# TCA_LP_FILTER.net
KiCad netlist of a schematic drawn in Altium Designer
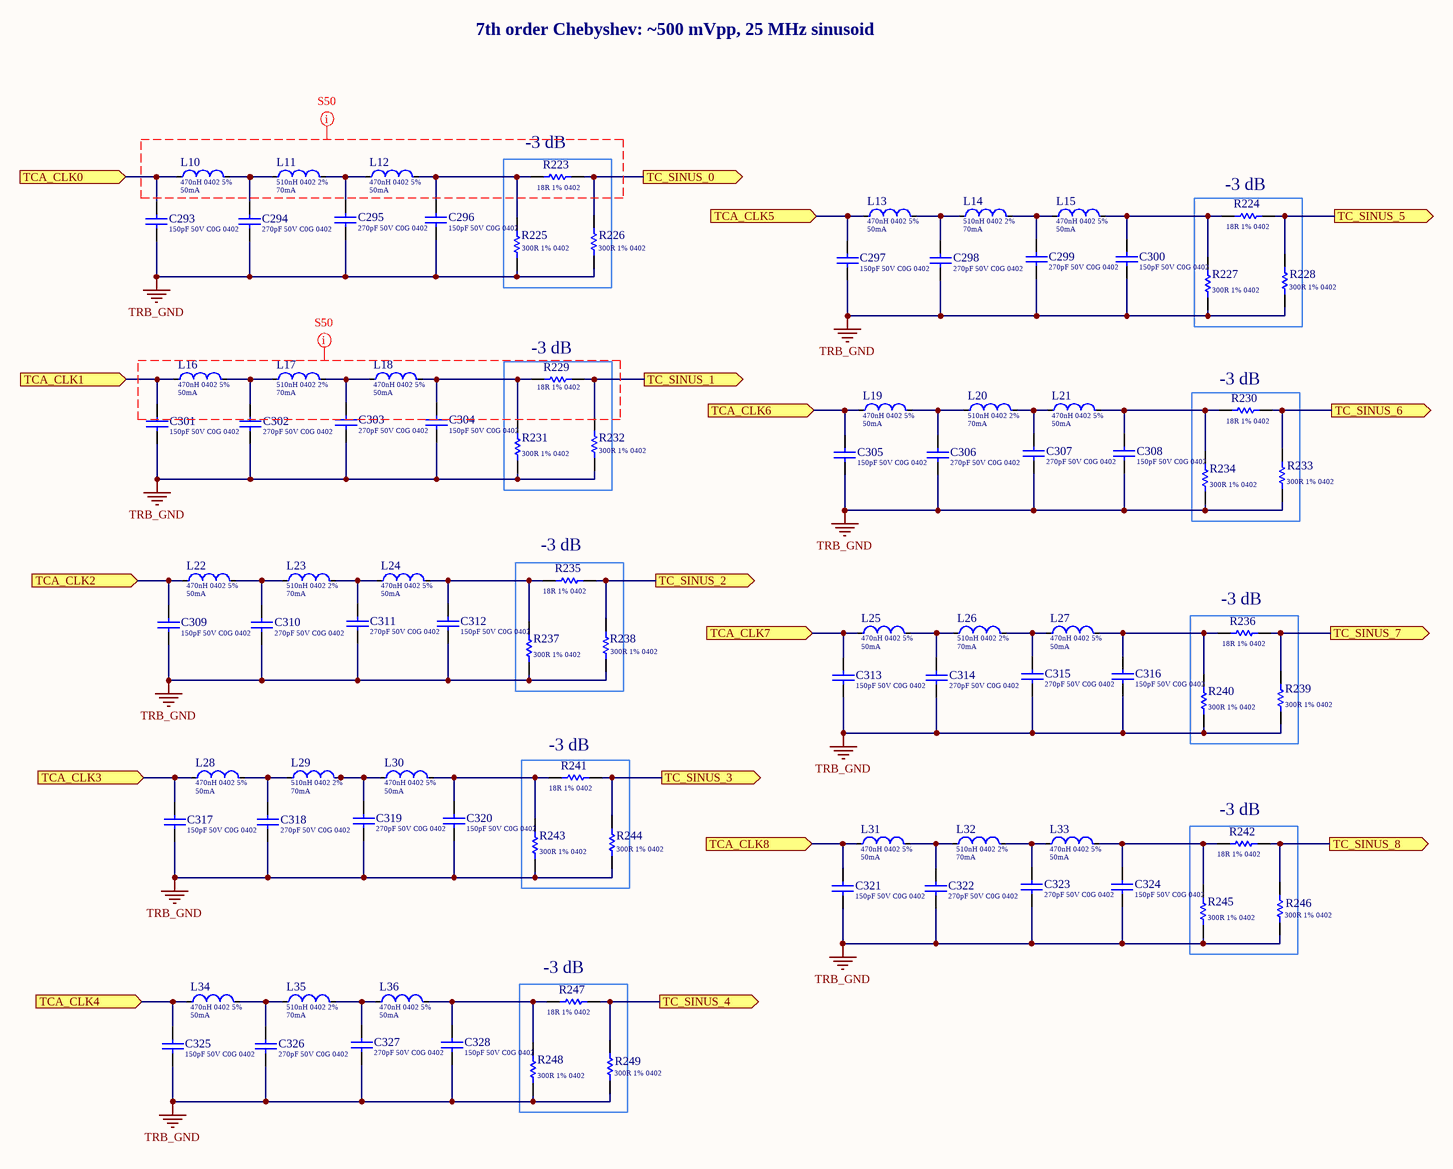
[diagram p0: TCA_LP_FILTER.SchDoc]

(export (version "E")
  (design (tool "Eeschema 10.0.6"))
  (components
    (comp (ref "C293")
      (value "Cap_TDK_CGA2B2C0G2A151J050BE_150pF")
      (footprint "Cap_TDK_CGA2B2C0G2A151J050BE_150pF")
      (description "CAP 150pF 50V C0G ±1% 0402 (1000 Metric) Thickness 1mm SMD")
      (fields (field (name "CAPACITANCE") "150pF 50V C0G 0402"))
      (libsource (lib "Cap_TDK_CGA2B2C0G2A151J050BE_150pF") (part "Cap_TDK_CGA2B2C0G2A151J050BE_150pF"))
    )
    (comp (ref "C294")
      (value "Cap_Murata_GCM1555C1H271FA16D_270pF")
      (footprint "Cap_Murata_GCM1555C1H271FA16D_270pF")
      (description "CAP 270pF 50V C0G ±1% 0402")
      (fields (field (name "CAPACITANCE") "270pF 50V C0G 0402"))
      (libsource (lib "Cap_Murata_GCM1555C1H271FA16D_270pF") (part "Cap_Murata_GCM1555C1H271FA16D_270pF"))
    )
    (comp (ref "C295")
      (value "Cap_Murata_GCM1555C1H271FA16D_270pF")
      (footprint "Cap_Murata_GCM1555C1H271FA16D_270pF")
      (description "CAP 270pF 50V C0G ±1% 0402")
      (fields (field (name "CAPACITANCE") "270pF 50V C0G 0402"))
      (libsource (lib "Cap_Murata_GCM1555C1H271FA16D_270pF") (part "Cap_Murata_GCM1555C1H271FA16D_270pF"))
    )
    (comp (ref "C296")
      (value "Cap_TDK_CGA2B2C0G2A151J050BE_150pF")
      (footprint "Cap_TDK_CGA2B2C0G2A151J050BE_150pF")
      (description "CAP 150pF 50V C0G ±1% 0402 (1000 Metric) Thickness 1mm SMD")
      (fields (field (name "CAPACITANCE") "150pF 50V C0G 0402"))
      (libsource (lib "Cap_TDK_CGA2B2C0G2A151J050BE_150pF") (part "Cap_TDK_CGA2B2C0G2A151J050BE_150pF"))
    )
    (comp (ref "C297")
      (value "Cap_TDK_CGA2B2C0G2A151J050BE_150pF")
      (footprint "Cap_TDK_CGA2B2C0G2A151J050BE_150pF")
      (description "CAP 150pF 50V C0G ±1% 0402 (1000 Metric) Thickness 1mm SMD")
      (fields (field (name "CAPACITANCE") "150pF 50V C0G 0402"))
      (libsource (lib "Cap_TDK_CGA2B2C0G2A151J050BE_150pF") (part "Cap_TDK_CGA2B2C0G2A151J050BE_150pF"))
    )
    (comp (ref "C298")
      (value "Cap_Murata_GCM1555C1H271FA16D_270pF")
      (footprint "Cap_Murata_GCM1555C1H271FA16D_270pF")
      (description "CAP 270pF 50V C0G ±1% 0402")
      (fields (field (name "CAPACITANCE") "270pF 50V C0G 0402"))
      (libsource (lib "Cap_Murata_GCM1555C1H271FA16D_270pF") (part "Cap_Murata_GCM1555C1H271FA16D_270pF"))
    )
    (comp (ref "C299")
      (value "Cap_Murata_GCM1555C1H271FA16D_270pF")
      (footprint "Cap_Murata_GCM1555C1H271FA16D_270pF")
      (description "CAP 270pF 50V C0G ±1% 0402")
      (fields (field (name "CAPACITANCE") "270pF 50V C0G 0402"))
      (libsource (lib "Cap_Murata_GCM1555C1H271FA16D_270pF") (part "Cap_Murata_GCM1555C1H271FA16D_270pF"))
    )
    (comp (ref "C300")
      (value "Cap_TDK_CGA2B2C0G2A151J050BE_150pF")
      (footprint "Cap_TDK_CGA2B2C0G2A151J050BE_150pF")
      (description "CAP 150pF 50V C0G ±1% 0402 (1000 Metric) Thickness 1mm SMD")
      (fields (field (name "CAPACITANCE") "150pF 50V C0G 0402"))
      (libsource (lib "Cap_TDK_CGA2B2C0G2A151J050BE_150pF") (part "Cap_TDK_CGA2B2C0G2A151J050BE_150pF"))
    )
    (comp (ref "C301")
      (value "Cap_TDK_CGA2B2C0G2A151J050BE_150pF")
      (footprint "Cap_TDK_CGA2B2C0G2A151J050BE_150pF")
      (description "CAP 150pF 50V C0G ±1% 0402 (1000 Metric) Thickness 1mm SMD")
      (fields (field (name "CAPACITANCE") "150pF 50V C0G 0402"))
      (libsource (lib "Cap_TDK_CGA2B2C0G2A151J050BE_150pF") (part "Cap_TDK_CGA2B2C0G2A151J050BE_150pF"))
    )
    (comp (ref "C302")
      (value "Cap_Murata_GCM1555C1H271FA16D_270pF")
      (footprint "Cap_Murata_GCM1555C1H271FA16D_270pF")
      (description "CAP 270pF 50V C0G ±1% 0402")
      (fields (field (name "CAPACITANCE") "270pF 50V C0G 0402"))
      (libsource (lib "Cap_Murata_GCM1555C1H271FA16D_270pF") (part "Cap_Murata_GCM1555C1H271FA16D_270pF"))
    )
    (comp (ref "C303")
      (value "Cap_Murata_GCM1555C1H271FA16D_270pF")
      (footprint "Cap_Murata_GCM1555C1H271FA16D_270pF")
      (description "CAP 270pF 50V C0G ±1% 0402")
      (fields (field (name "CAPACITANCE") "270pF 50V C0G 0402"))
      (libsource (lib "Cap_Murata_GCM1555C1H271FA16D_270pF") (part "Cap_Murata_GCM1555C1H271FA16D_270pF"))
    )
    (comp (ref "C304")
      (value "Cap_TDK_CGA2B2C0G2A151J050BE_150pF")
      (footprint "Cap_TDK_CGA2B2C0G2A151J050BE_150pF")
      (description "CAP 150pF 50V C0G ±1% 0402 (1000 Metric) Thickness 1mm SMD")
      (fields (field (name "CAPACITANCE") "150pF 50V C0G 0402"))
      (libsource (lib "Cap_TDK_CGA2B2C0G2A151J050BE_150pF") (part "Cap_TDK_CGA2B2C0G2A151J050BE_150pF"))
    )
    (comp (ref "C305")
      (value "Cap_TDK_CGA2B2C0G2A151J050BE_150pF")
      (footprint "Cap_TDK_CGA2B2C0G2A151J050BE_150pF")
      (description "CAP 150pF 50V C0G ±1% 0402 (1000 Metric) Thickness 1mm SMD")
      (fields (field (name "CAPACITANCE") "150pF 50V C0G 0402"))
      (libsource (lib "Cap_TDK_CGA2B2C0G2A151J050BE_150pF") (part "Cap_TDK_CGA2B2C0G2A151J050BE_150pF"))
    )
    (comp (ref "C306")
      (value "Cap_Murata_GCM1555C1H271FA16D_270pF")
      (footprint "Cap_Murata_GCM1555C1H271FA16D_270pF")
      (description "CAP 270pF 50V C0G ±1% 0402")
      (fields (field (name "CAPACITANCE") "270pF 50V C0G 0402"))
      (libsource (lib "Cap_Murata_GCM1555C1H271FA16D_270pF") (part "Cap_Murata_GCM1555C1H271FA16D_270pF"))
    )
    (comp (ref "C307")
      (value "Cap_Murata_GCM1555C1H271FA16D_270pF")
      (footprint "Cap_Murata_GCM1555C1H271FA16D_270pF")
      (description "CAP 270pF 50V C0G ±1% 0402")
      (fields (field (name "CAPACITANCE") "270pF 50V C0G 0402"))
      (libsource (lib "Cap_Murata_GCM1555C1H271FA16D_270pF") (part "Cap_Murata_GCM1555C1H271FA16D_270pF"))
    )
    (comp (ref "C308")
      (value "Cap_TDK_CGA2B2C0G2A151J050BE_150pF")
      (footprint "Cap_TDK_CGA2B2C0G2A151J050BE_150pF")
      (description "CAP 150pF 50V C0G ±1% 0402 (1000 Metric) Thickness 1mm SMD")
      (fields (field (name "CAPACITANCE") "150pF 50V C0G 0402"))
      (libsource (lib "Cap_TDK_CGA2B2C0G2A151J050BE_150pF") (part "Cap_TDK_CGA2B2C0G2A151J050BE_150pF"))
    )
    (comp (ref "C309")
      (value "Cap_TDK_CGA2B2C0G2A151J050BE_150pF")
      (footprint "Cap_TDK_CGA2B2C0G2A151J050BE_150pF")
      (description "CAP 150pF 50V C0G ±1% 0402 (1000 Metric) Thickness 1mm SMD")
      (fields (field (name "CAPACITANCE") "150pF 50V C0G 0402"))
      (libsource (lib "Cap_TDK_CGA2B2C0G2A151J050BE_150pF") (part "Cap_TDK_CGA2B2C0G2A151J050BE_150pF"))
    )
    (comp (ref "C310")
      (value "Cap_Murata_GCM1555C1H271FA16D_270pF")
      (footprint "Cap_Murata_GCM1555C1H271FA16D_270pF")
      (description "CAP 270pF 50V C0G ±1% 0402")
      (fields (field (name "CAPACITANCE") "270pF 50V C0G 0402"))
      (libsource (lib "Cap_Murata_GCM1555C1H271FA16D_270pF") (part "Cap_Murata_GCM1555C1H271FA16D_270pF"))
    )
    (comp (ref "C311")
      (value "Cap_Murata_GCM1555C1H271FA16D_270pF")
      (footprint "Cap_Murata_GCM1555C1H271FA16D_270pF")
      (description "CAP 270pF 50V C0G ±1% 0402")
      (fields (field (name "CAPACITANCE") "270pF 50V C0G 0402"))
      (libsource (lib "Cap_Murata_GCM1555C1H271FA16D_270pF") (part "Cap_Murata_GCM1555C1H271FA16D_270pF"))
    )
    (comp (ref "C312")
      (value "Cap_TDK_CGA2B2C0G2A151J050BE_150pF")
      (footprint "Cap_TDK_CGA2B2C0G2A151J050BE_150pF")
      (description "CAP 150pF 50V C0G ±1% 0402 (1000 Metric) Thickness 1mm SMD")
      (fields (field (name "CAPACITANCE") "150pF 50V C0G 0402"))
      (libsource (lib "Cap_TDK_CGA2B2C0G2A151J050BE_150pF") (part "Cap_TDK_CGA2B2C0G2A151J050BE_150pF"))
    )
    (comp (ref "C313")
      (value "Cap_TDK_CGA2B2C0G2A151J050BE_150pF")
      (footprint "Cap_TDK_CGA2B2C0G2A151J050BE_150pF")
      (description "CAP 150pF 50V C0G ±1% 0402 (1000 Metric) Thickness 1mm SMD")
      (fields (field (name "CAPACITANCE") "150pF 50V C0G 0402"))
      (libsource (lib "Cap_TDK_CGA2B2C0G2A151J050BE_150pF") (part "Cap_TDK_CGA2B2C0G2A151J050BE_150pF"))
    )
    (comp (ref "C314")
      (value "Cap_Murata_GCM1555C1H271FA16D_270pF")
      (footprint "Cap_Murata_GCM1555C1H271FA16D_270pF")
      (description "CAP 270pF 50V C0G ±1% 0402")
      (fields (field (name "CAPACITANCE") "270pF 50V C0G 0402"))
      (libsource (lib "Cap_Murata_GCM1555C1H271FA16D_270pF") (part "Cap_Murata_GCM1555C1H271FA16D_270pF"))
    )
    (comp (ref "C315")
      (value "Cap_Murata_GCM1555C1H271FA16D_270pF")
      (footprint "Cap_Murata_GCM1555C1H271FA16D_270pF")
      (description "CAP 270pF 50V C0G ±1% 0402")
      (fields (field (name "CAPACITANCE") "270pF 50V C0G 0402"))
      (libsource (lib "Cap_Murata_GCM1555C1H271FA16D_270pF") (part "Cap_Murata_GCM1555C1H271FA16D_270pF"))
    )
    (comp (ref "C316")
      (value "Cap_TDK_CGA2B2C0G2A151J050BE_150pF")
      (footprint "Cap_TDK_CGA2B2C0G2A151J050BE_150pF")
      (description "CAP 150pF 50V C0G ±1% 0402 (1000 Metric) Thickness 1mm SMD")
      (fields (field (name "CAPACITANCE") "150pF 50V C0G 0402"))
      (libsource (lib "Cap_TDK_CGA2B2C0G2A151J050BE_150pF") (part "Cap_TDK_CGA2B2C0G2A151J050BE_150pF"))
    )
    (comp (ref "C317")
      (value "Cap_TDK_CGA2B2C0G2A151J050BE_150pF")
      (footprint "Cap_TDK_CGA2B2C0G2A151J050BE_150pF")
      (description "CAP 150pF 50V C0G ±1% 0402 (1000 Metric) Thickness 1mm SMD")
      (fields (field (name "CAPACITANCE") "150pF 50V C0G 0402"))
      (libsource (lib "Cap_TDK_CGA2B2C0G2A151J050BE_150pF") (part "Cap_TDK_CGA2B2C0G2A151J050BE_150pF"))
    )
    (comp (ref "C318")
      (value "Cap_Murata_GCM1555C1H271FA16D_270pF")
      (footprint "Cap_Murata_GCM1555C1H271FA16D_270pF")
      (description "CAP 270pF 50V C0G ±1% 0402")
      (fields (field (name "CAPACITANCE") "270pF 50V C0G 0402"))
      (libsource (lib "Cap_Murata_GCM1555C1H271FA16D_270pF") (part "Cap_Murata_GCM1555C1H271FA16D_270pF"))
    )
    (comp (ref "C319")
      (value "Cap_Murata_GCM1555C1H271FA16D_270pF")
      (footprint "Cap_Murata_GCM1555C1H271FA16D_270pF")
      (description "CAP 270pF 50V C0G ±1% 0402")
      (fields (field (name "CAPACITANCE") "270pF 50V C0G 0402"))
      (libsource (lib "Cap_Murata_GCM1555C1H271FA16D_270pF") (part "Cap_Murata_GCM1555C1H271FA16D_270pF"))
    )
    (comp (ref "C320")
      (value "Cap_TDK_CGA2B2C0G2A151J050BE_150pF")
      (footprint "Cap_TDK_CGA2B2C0G2A151J050BE_150pF")
      (description "CAP 150pF 50V C0G ±1% 0402 (1000 Metric) Thickness 1mm SMD")
      (fields (field (name "CAPACITANCE") "150pF 50V C0G 0402"))
      (libsource (lib "Cap_TDK_CGA2B2C0G2A151J050BE_150pF") (part "Cap_TDK_CGA2B2C0G2A151J050BE_150pF"))
    )
    (comp (ref "C321")
      (value "Cap_TDK_CGA2B2C0G2A151J050BE_150pF")
      (footprint "Cap_TDK_CGA2B2C0G2A151J050BE_150pF")
      (description "CAP 150pF 50V C0G ±1% 0402 (1000 Metric) Thickness 1mm SMD")
      (fields (field (name "CAPACITANCE") "150pF 50V C0G 0402"))
      (libsource (lib "Cap_TDK_CGA2B2C0G2A151J050BE_150pF") (part "Cap_TDK_CGA2B2C0G2A151J050BE_150pF"))
    )
    (comp (ref "C322")
      (value "Cap_Murata_GCM1555C1H271FA16D_270pF")
      (footprint "Cap_Murata_GCM1555C1H271FA16D_270pF")
      (description "CAP 270pF 50V C0G ±1% 0402")
      (fields (field (name "CAPACITANCE") "270pF 50V C0G 0402"))
      (libsource (lib "Cap_Murata_GCM1555C1H271FA16D_270pF") (part "Cap_Murata_GCM1555C1H271FA16D_270pF"))
    )
    (comp (ref "C323")
      (value "Cap_Murata_GCM1555C1H271FA16D_270pF")
      (footprint "Cap_Murata_GCM1555C1H271FA16D_270pF")
      (description "CAP 270pF 50V C0G ±1% 0402")
      (fields (field (name "CAPACITANCE") "270pF 50V C0G 0402"))
      (libsource (lib "Cap_Murata_GCM1555C1H271FA16D_270pF") (part "Cap_Murata_GCM1555C1H271FA16D_270pF"))
    )
    (comp (ref "C324")
      (value "Cap_TDK_CGA2B2C0G2A151J050BE_150pF")
      (footprint "Cap_TDK_CGA2B2C0G2A151J050BE_150pF")
      (description "CAP 150pF 50V C0G ±1% 0402 (1000 Metric) Thickness 1mm SMD")
      (fields (field (name "CAPACITANCE") "150pF 50V C0G 0402"))
      (libsource (lib "Cap_TDK_CGA2B2C0G2A151J050BE_150pF") (part "Cap_TDK_CGA2B2C0G2A151J050BE_150pF"))
    )
    (comp (ref "C325")
      (value "Cap_TDK_CGA2B2C0G2A151J050BE_150pF")
      (footprint "Cap_TDK_CGA2B2C0G2A151J050BE_150pF")
      (description "CAP 150pF 50V C0G ±1% 0402 (1000 Metric) Thickness 1mm SMD")
      (fields (field (name "CAPACITANCE") "150pF 50V C0G 0402"))
      (libsource (lib "Cap_TDK_CGA2B2C0G2A151J050BE_150pF") (part "Cap_TDK_CGA2B2C0G2A151J050BE_150pF"))
    )
    (comp (ref "C326")
      (value "Cap_Murata_GCM1555C1H271FA16D_270pF")
      (footprint "Cap_Murata_GCM1555C1H271FA16D_270pF")
      (description "CAP 270pF 50V C0G ±1% 0402")
      (fields (field (name "CAPACITANCE") "270pF 50V C0G 0402"))
      (libsource (lib "Cap_Murata_GCM1555C1H271FA16D_270pF") (part "Cap_Murata_GCM1555C1H271FA16D_270pF"))
    )
    (comp (ref "C327")
      (value "Cap_Murata_GCM1555C1H271FA16D_270pF")
      (footprint "Cap_Murata_GCM1555C1H271FA16D_270pF")
      (description "CAP 270pF 50V C0G ±1% 0402")
      (fields (field (name "CAPACITANCE") "270pF 50V C0G 0402"))
      (libsource (lib "Cap_Murata_GCM1555C1H271FA16D_270pF") (part "Cap_Murata_GCM1555C1H271FA16D_270pF"))
    )
    (comp (ref "C328")
      (value "Cap_TDK_CGA2B2C0G2A151J050BE_150pF")
      (footprint "Cap_TDK_CGA2B2C0G2A151J050BE_150pF")
      (description "CAP 150pF 50V C0G ±1% 0402 (1000 Metric) Thickness 1mm SMD")
      (fields (field (name "CAPACITANCE") "150pF 50V C0G 0402"))
      (libsource (lib "Cap_TDK_CGA2B2C0G2A151J050BE_150pF") (part "Cap_TDK_CGA2B2C0G2A151J050BE_150pF"))
    )
    (comp (ref "L10")
      (value "470nH 0402 5%")
      (footprint "TDK_MLF1005GR47JT000_0")
      (description "IND 470nH Shielded Multilayer Inductor 50mA 420 mOhm Max 0402 (1005 Metric)")
      (fields
        (field (name "PART NUMBER") "MLF1005GR47JT000")
        (field (name "MANUFACTURER") "TDK")
        (field (name "CURRENT RATING") "50mA")
      )
      (libsource (lib "Ind_TDK_MLF1005GR47JT000_470nH") (part "Ind_TDK_MLF1005GR47JT000"))
    )
    (comp (ref "L11")
      (value "510nH 0402 2%")
      (footprint "TDK_MHQ1005PR51GT000_0")
      (description "IND 510nH Shielded Multilayer Inductor 70mA 10.2 Ohm Max 0402 (1005 Metric)")
      (fields
        (field (name "PART NUMBER") "MHQ1005PR51GT000")
        (field (name "MANUFACTURER") "TDK")
        (field (name "CURRENT RATING") "70mA")
      )
      (libsource (lib "Ind_TDK_MHQ1005PR51GT000_510nH") (part "Ind_TDK_MHQ1005PR51GT000"))
    )
    (comp (ref "L12")
      (value "470nH 0402 5%")
      (footprint "TDK_MLF1005GR47JT000_0")
      (description "IND 470nH Shielded Multilayer Inductor 50mA 420 mOhm Max 0402 (1005 Metric)")
      (fields
        (field (name "PART NUMBER") "MLF1005GR47JT000")
        (field (name "MANUFACTURER") "TDK")
        (field (name "CURRENT RATING") "50mA")
      )
      (libsource (lib "Ind_TDK_MLF1005GR47JT000_470nH") (part "Ind_TDK_MLF1005GR47JT000"))
    )
    (comp (ref "L13")
      (value "470nH 0402 5%")
      (footprint "TDK_MLF1005GR47JT000_0")
      (description "IND 470nH Shielded Multilayer Inductor 50mA 420 mOhm Max 0402 (1005 Metric)")
      (fields
        (field (name "PART NUMBER") "MLF1005GR47JT000")
        (field (name "MANUFACTURER") "TDK")
        (field (name "CURRENT RATING") "50mA")
      )
      (libsource (lib "Ind_TDK_MLF1005GR47JT000_470nH") (part "Ind_TDK_MLF1005GR47JT000"))
    )
    (comp (ref "L14")
      (value "510nH 0402 2%")
      (footprint "TDK_MHQ1005PR51GT000_0")
      (description "IND 510nH Shielded Multilayer Inductor 70mA 10.2 Ohm Max 0402 (1005 Metric)")
      (fields
        (field (name "PART NUMBER") "MHQ1005PR51GT000")
        (field (name "MANUFACTURER") "TDK")
        (field (name "CURRENT RATING") "70mA")
      )
      (libsource (lib "Ind_TDK_MHQ1005PR51GT000_510nH") (part "Ind_TDK_MHQ1005PR51GT000"))
    )
    (comp (ref "L15")
      (value "470nH 0402 5%")
      (footprint "TDK_MLF1005GR47JT000_0")
      (description "IND 470nH Shielded Multilayer Inductor 50mA 420 mOhm Max 0402 (1005 Metric)")
      (fields
        (field (name "PART NUMBER") "MLF1005GR47JT000")
        (field (name "MANUFACTURER") "TDK")
        (field (name "CURRENT RATING") "50mA")
      )
      (libsource (lib "Ind_TDK_MLF1005GR47JT000_470nH") (part "Ind_TDK_MLF1005GR47JT000"))
    )
    (comp (ref "L16")
      (value "470nH 0402 5%")
      (footprint "TDK_MLF1005GR47JT000_0")
      (description "IND 470nH Shielded Multilayer Inductor 50mA 420 mOhm Max 0402 (1005 Metric)")
      (fields
        (field (name "PART NUMBER") "MLF1005GR47JT000")
        (field (name "MANUFACTURER") "TDK")
        (field (name "CURRENT RATING") "50mA")
      )
      (libsource (lib "Ind_TDK_MLF1005GR47JT000_470nH") (part "Ind_TDK_MLF1005GR47JT000"))
    )
    (comp (ref "L17")
      (value "510nH 0402 2%")
      (footprint "TDK_MHQ1005PR51GT000_0")
      (description "IND 510nH Shielded Multilayer Inductor 70mA 10.2 Ohm Max 0402 (1005 Metric)")
      (fields
        (field (name "PART NUMBER") "MHQ1005PR51GT000")
        (field (name "MANUFACTURER") "TDK")
        (field (name "CURRENT RATING") "70mA")
      )
      (libsource (lib "Ind_TDK_MHQ1005PR51GT000_510nH") (part "Ind_TDK_MHQ1005PR51GT000"))
    )
    (comp (ref "L18")
      (value "470nH 0402 5%")
      (footprint "TDK_MLF1005GR47JT000_0")
      (description "IND 470nH Shielded Multilayer Inductor 50mA 420 mOhm Max 0402 (1005 Metric)")
      (fields
        (field (name "PART NUMBER") "MLF1005GR47JT000")
        (field (name "MANUFACTURER") "TDK")
        (field (name "CURRENT RATING") "50mA")
      )
      (libsource (lib "Ind_TDK_MLF1005GR47JT000_470nH") (part "Ind_TDK_MLF1005GR47JT000"))
    )
    (comp (ref "L19")
      (value "470nH 0402 5%")
      (footprint "TDK_MLF1005GR47JT000_0")
      (description "IND 470nH Shielded Multilayer Inductor 50mA 420 mOhm Max 0402 (1005 Metric)")
      (fields
        (field (name "PART NUMBER") "MLF1005GR47JT000")
        (field (name "MANUFACTURER") "TDK")
        (field (name "CURRENT RATING") "50mA")
      )
      (libsource (lib "Ind_TDK_MLF1005GR47JT000_470nH") (part "Ind_TDK_MLF1005GR47JT000"))
    )
    (comp (ref "L20")
      (value "510nH 0402 2%")
      (footprint "TDK_MHQ1005PR51GT000_0")
      (description "IND 510nH Shielded Multilayer Inductor 70mA 10.2 Ohm Max 0402 (1005 Metric)")
      (fields
        (field (name "PART NUMBER") "MHQ1005PR51GT000")
        (field (name "MANUFACTURER") "TDK")
        (field (name "CURRENT RATING") "70mA")
      )
      (libsource (lib "Ind_TDK_MHQ1005PR51GT000_510nH") (part "Ind_TDK_MHQ1005PR51GT000"))
    )
    (comp (ref "L21")
      (value "470nH 0402 5%")
      (footprint "TDK_MLF1005GR47JT000_0")
      (description "IND 470nH Shielded Multilayer Inductor 50mA 420 mOhm Max 0402 (1005 Metric)")
      (fields
        (field (name "PART NUMBER") "MLF1005GR47JT000")
        (field (name "MANUFACTURER") "TDK")
        (field (name "CURRENT RATING") "50mA")
      )
      (libsource (lib "Ind_TDK_MLF1005GR47JT000_470nH") (part "Ind_TDK_MLF1005GR47JT000"))
    )
    (comp (ref "L22")
      (value "470nH 0402 5%")
      (footprint "TDK_MLF1005GR47JT000_0")
      (description "IND 470nH Shielded Multilayer Inductor 50mA 420 mOhm Max 0402 (1005 Metric)")
      (fields
        (field (name "PART NUMBER") "MLF1005GR47JT000")
        (field (name "MANUFACTURER") "TDK")
        (field (name "CURRENT RATING") "50mA")
      )
      (libsource (lib "Ind_TDK_MLF1005GR47JT000_470nH") (part "Ind_TDK_MLF1005GR47JT000"))
    )
    (comp (ref "L23")
      (value "510nH 0402 2%")
      (footprint "TDK_MHQ1005PR51GT000_0")
      (description "IND 510nH Shielded Multilayer Inductor 70mA 10.2 Ohm Max 0402 (1005 Metric)")
      (fields
        (field (name "PART NUMBER") "MHQ1005PR51GT000")
        (field (name "MANUFACTURER") "TDK")
        (field (name "CURRENT RATING") "70mA")
      )
      (libsource (lib "Ind_TDK_MHQ1005PR51GT000_510nH") (part "Ind_TDK_MHQ1005PR51GT000"))
    )
    (comp (ref "L24")
      (value "470nH 0402 5%")
      (footprint "TDK_MLF1005GR47JT000_0")
      (description "IND 470nH Shielded Multilayer Inductor 50mA 420 mOhm Max 0402 (1005 Metric)")
      (fields
        (field (name "PART NUMBER") "MLF1005GR47JT000")
        (field (name "MANUFACTURER") "TDK")
        (field (name "CURRENT RATING") "50mA")
      )
      (libsource (lib "Ind_TDK_MLF1005GR47JT000_470nH") (part "Ind_TDK_MLF1005GR47JT000"))
    )
    (comp (ref "L25")
      (value "470nH 0402 5%")
      (footprint "TDK_MLF1005GR47JT000_0")
      (description "IND 470nH Shielded Multilayer Inductor 50mA 420 mOhm Max 0402 (1005 Metric)")
      (fields
        (field (name "PART NUMBER") "MLF1005GR47JT000")
        (field (name "MANUFACTURER") "TDK")
        (field (name "CURRENT RATING") "50mA")
      )
      (libsource (lib "Ind_TDK_MLF1005GR47JT000_470nH") (part "Ind_TDK_MLF1005GR47JT000"))
    )
    (comp (ref "L26")
      (value "510nH 0402 2%")
      (footprint "TDK_MHQ1005PR51GT000_0")
      (description "IND 510nH Shielded Multilayer Inductor 70mA 10.2 Ohm Max 0402 (1005 Metric)")
      (fields
        (field (name "PART NUMBER") "MHQ1005PR51GT000")
        (field (name "MANUFACTURER") "TDK")
        (field (name "CURRENT RATING") "70mA")
      )
      (libsource (lib "Ind_TDK_MHQ1005PR51GT000_510nH") (part "Ind_TDK_MHQ1005PR51GT000"))
    )
    (comp (ref "L27")
      (value "470nH 0402 5%")
      (footprint "TDK_MLF1005GR47JT000_0")
      (description "IND 470nH Shielded Multilayer Inductor 50mA 420 mOhm Max 0402 (1005 Metric)")
      (fields
        (field (name "PART NUMBER") "MLF1005GR47JT000")
        (field (name "MANUFACTURER") "TDK")
        (field (name "CURRENT RATING") "50mA")
      )
      (libsource (lib "Ind_TDK_MLF1005GR47JT000_470nH") (part "Ind_TDK_MLF1005GR47JT000"))
    )
    (comp (ref "L28")
      (value "470nH 0402 5%")
      (footprint "TDK_MLF1005GR47JT000_0")
      (description "IND 470nH Shielded Multilayer Inductor 50mA 420 mOhm Max 0402 (1005 Metric)")
      (fields
        (field (name "PART NUMBER") "MLF1005GR47JT000")
        (field (name "MANUFACTURER") "TDK")
        (field (name "CURRENT RATING") "50mA")
      )
      (libsource (lib "Ind_TDK_MLF1005GR47JT000_470nH") (part "Ind_TDK_MLF1005GR47JT000"))
    )
    (comp (ref "L29")
      (value "510nH 0402 2%")
      (footprint "TDK_MHQ1005PR51GT000_0")
      (description "IND 510nH Shielded Multilayer Inductor 70mA 10.2 Ohm Max 0402 (1005 Metric)")
      (fields
        (field (name "PART NUMBER") "MHQ1005PR51GT000")
        (field (name "MANUFACTURER") "TDK")
        (field (name "CURRENT RATING") "70mA")
      )
      (libsource (lib "Ind_TDK_MHQ1005PR51GT000_510nH") (part "Ind_TDK_MHQ1005PR51GT000"))
    )
    (comp (ref "L30")
      (value "470nH 0402 5%")
      (footprint "TDK_MLF1005GR47JT000_0")
      (description "IND 470nH Shielded Multilayer Inductor 50mA 420 mOhm Max 0402 (1005 Metric)")
      (fields
        (field (name "PART NUMBER") "MLF1005GR47JT000")
        (field (name "MANUFACTURER") "TDK")
        (field (name "CURRENT RATING") "50mA")
      )
      (libsource (lib "Ind_TDK_MLF1005GR47JT000_470nH") (part "Ind_TDK_MLF1005GR47JT000"))
    )
    (comp (ref "L31")
      (value "470nH 0402 5%")
      (footprint "TDK_MLF1005GR47JT000_0")
      (description "IND 470nH Shielded Multilayer Inductor 50mA 420 mOhm Max 0402 (1005 Metric)")
      (fields
        (field (name "PART NUMBER") "MLF1005GR47JT000")
        (field (name "MANUFACTURER") "TDK")
        (field (name "CURRENT RATING") "50mA")
      )
      (libsource (lib "Ind_TDK_MLF1005GR47JT000_470nH") (part "Ind_TDK_MLF1005GR47JT000"))
    )
    (comp (ref "L32")
      (value "510nH 0402 2%")
      (footprint "TDK_MHQ1005PR51GT000_0")
      (description "IND 510nH Shielded Multilayer Inductor 70mA 10.2 Ohm Max 0402 (1005 Metric)")
      (fields
        (field (name "PART NUMBER") "MHQ1005PR51GT000")
        (field (name "MANUFACTURER") "TDK")
        (field (name "CURRENT RATING") "70mA")
      )
      (libsource (lib "Ind_TDK_MHQ1005PR51GT000_510nH") (part "Ind_TDK_MHQ1005PR51GT000"))
    )
    (comp (ref "L33")
      (value "470nH 0402 5%")
      (footprint "TDK_MLF1005GR47JT000_0")
      (description "IND 470nH Shielded Multilayer Inductor 50mA 420 mOhm Max 0402 (1005 Metric)")
      (fields
        (field (name "PART NUMBER") "MLF1005GR47JT000")
        (field (name "MANUFACTURER") "TDK")
        (field (name "CURRENT RATING") "50mA")
      )
      (libsource (lib "Ind_TDK_MLF1005GR47JT000_470nH") (part "Ind_TDK_MLF1005GR47JT000"))
    )
    (comp (ref "L34")
      (value "470nH 0402 5%")
      (footprint "TDK_MLF1005GR47JT000_0")
      (description "IND 470nH Shielded Multilayer Inductor 50mA 420 mOhm Max 0402 (1005 Metric)")
      (fields
        (field (name "PART NUMBER") "MLF1005GR47JT000")
        (field (name "MANUFACTURER") "TDK")
        (field (name "CURRENT RATING") "50mA")
      )
      (libsource (lib "Ind_TDK_MLF1005GR47JT000_470nH") (part "Ind_TDK_MLF1005GR47JT000"))
    )
    (comp (ref "L35")
      (value "510nH 0402 2%")
      (footprint "TDK_MHQ1005PR51GT000_0")
      (description "IND 510nH Shielded Multilayer Inductor 70mA 10.2 Ohm Max 0402 (1005 Metric)")
      (fields
        (field (name "PART NUMBER") "MHQ1005PR51GT000")
        (field (name "MANUFACTURER") "TDK")
        (field (name "CURRENT RATING") "70mA")
      )
      (libsource (lib "Ind_TDK_MHQ1005PR51GT000_510nH") (part "Ind_TDK_MHQ1005PR51GT000"))
    )
    (comp (ref "L36")
      (value "470nH 0402 5%")
      (footprint "TDK_MLF1005GR47JT000_0")
      (description "IND 470nH Shielded Multilayer Inductor 50mA 420 mOhm Max 0402 (1005 Metric)")
      (fields
        (field (name "PART NUMBER") "MLF1005GR47JT000")
        (field (name "MANUFACTURER") "TDK")
        (field (name "CURRENT RATING") "50mA")
      )
      (libsource (lib "Ind_TDK_MLF1005GR47JT000_470nH") (part "Ind_TDK_MLF1005GR47JT000"))
    )
    (comp (ref "R223")
      (value "18R 1% 0402")
      (footprint "RESC0402(1005)_L")
      (description "18R 0.063W 1% 0402 (1005 Metric)  SMD")
      (fields (field (name "TOLERANCE") "1 %") (field (name "POWER") "0.063 W"))
      (libsource (lib "Altium Content Vault") (part "RES"))
    )
    (comp (ref "R224")
      (value "18R 1% 0402")
      (footprint "RESC0402(1005)_L")
      (description "18R 0.063W 1% 0402 (1005 Metric)  SMD")
      (fields (field (name "TOLERANCE") "1 %") (field (name "POWER") "0.063 W"))
      (libsource (lib "Altium Content Vault") (part "RES"))
    )
    (comp (ref "R225")
      (value "300R 1% 0402")
      (footprint "RESC0402(1005)_L")
      (description "300R 0.063W 1% 0402 (1005 Metric)  SMD")
      (fields (field (name "TOLERANCE") "1 %") (field (name "POWER") "0.063 W"))
      (libsource (lib "Altium Content Vault") (part "RES"))
    )
    (comp (ref "R226")
      (value "300R 1% 0402")
      (footprint "RESC0402(1005)_L")
      (description "300R 0.063W 1% 0402 (1005 Metric)  SMD")
      (fields (field (name "TOLERANCE") "1 %") (field (name "POWER") "0.063 W"))
      (libsource (lib "Altium Content Vault") (part "RES"))
    )
    (comp (ref "R227")
      (value "300R 1% 0402")
      (footprint "RESC0402(1005)_L")
      (description "300R 0.063W 1% 0402 (1005 Metric)  SMD")
      (fields (field (name "TOLERANCE") "1 %") (field (name "POWER") "0.063 W"))
      (libsource (lib "Altium Content Vault") (part "RES"))
    )
    (comp (ref "R228")
      (value "300R 1% 0402")
      (footprint "RESC0402(1005)_L")
      (description "300R 0.063W 1% 0402 (1005 Metric)  SMD")
      (fields (field (name "TOLERANCE") "1 %") (field (name "POWER") "0.063 W"))
      (libsource (lib "Altium Content Vault") (part "RES"))
    )
    (comp (ref "R229")
      (value "18R 1% 0402")
      (footprint "RESC0402(1005)_L")
      (description "18R 0.063W 1% 0402 (1005 Metric)  SMD")
      (fields (field (name "TOLERANCE") "1 %") (field (name "POWER") "0.063 W"))
      (libsource (lib "Altium Content Vault") (part "RES"))
    )
    (comp (ref "R230")
      (value "18R 1% 0402")
      (footprint "RESC0402(1005)_L")
      (description "18R 0.063W 1% 0402 (1005 Metric)  SMD")
      (fields (field (name "TOLERANCE") "1 %") (field (name "POWER") "0.063 W"))
      (libsource (lib "Altium Content Vault") (part "RES"))
    )
    (comp (ref "R231")
      (value "300R 1% 0402")
      (footprint "RESC0402(1005)_L")
      (description "300R 0.063W 1% 0402 (1005 Metric)  SMD")
      (fields (field (name "TOLERANCE") "1 %") (field (name "POWER") "0.063 W"))
      (libsource (lib "Altium Content Vault") (part "RES"))
    )
    (comp (ref "R232")
      (value "300R 1% 0402")
      (footprint "RESC0402(1005)_L")
      (description "300R 0.063W 1% 0402 (1005 Metric)  SMD")
      (fields (field (name "TOLERANCE") "1 %") (field (name "POWER") "0.063 W"))
      (libsource (lib "Altium Content Vault") (part "RES"))
    )
    (comp (ref "R233")
      (value "300R 1% 0402")
      (footprint "RESC0402(1005)_L")
      (description "300R 0.063W 1% 0402 (1005 Metric)  SMD")
      (fields (field (name "TOLERANCE") "1 %") (field (name "POWER") "0.063 W"))
      (libsource (lib "Altium Content Vault") (part "RES"))
    )
    (comp (ref "R234")
      (value "300R 1% 0402")
      (footprint "RESC0402(1005)_L")
      (description "300R 0.063W 1% 0402 (1005 Metric)  SMD")
      (fields (field (name "TOLERANCE") "1 %") (field (name "POWER") "0.063 W"))
      (libsource (lib "Altium Content Vault") (part "RES"))
    )
    (comp (ref "R235")
      (value "18R 1% 0402")
      (footprint "RESC0402(1005)_L")
      (description "18R 0.063W 1% 0402 (1005 Metric)  SMD")
      (fields (field (name "TOLERANCE") "1 %") (field (name "POWER") "0.063 W"))
      (libsource (lib "Altium Content Vault") (part "RES"))
    )
    (comp (ref "R236")
      (value "18R 1% 0402")
      (footprint "RESC0402(1005)_L")
      (description "18R 0.063W 1% 0402 (1005 Metric)  SMD")
      (fields (field (name "TOLERANCE") "1 %") (field (name "POWER") "0.063 W"))
      (libsource (lib "Altium Content Vault") (part "RES"))
    )
    (comp (ref "R237")
      (value "300R 1% 0402")
      (footprint "RESC0402(1005)_L")
      (description "300R 0.063W 1% 0402 (1005 Metric)  SMD")
      (fields (field (name "TOLERANCE") "1 %") (field (name "POWER") "0.063 W"))
      (libsource (lib "Altium Content Vault") (part "RES"))
    )
    (comp (ref "R238")
      (value "300R 1% 0402")
      (footprint "RESC0402(1005)_L")
      (description "300R 0.063W 1% 0402 (1005 Metric)  SMD")
      (fields (field (name "TOLERANCE") "1 %") (field (name "POWER") "0.063 W"))
      (libsource (lib "Altium Content Vault") (part "RES"))
    )
    (comp (ref "R239")
      (value "300R 1% 0402")
      (footprint "RESC0402(1005)_L")
      (description "300R 0.063W 1% 0402 (1005 Metric)  SMD")
      (fields (field (name "TOLERANCE") "1 %") (field (name "POWER") "0.063 W"))
      (libsource (lib "Altium Content Vault") (part "RES"))
    )
    (comp (ref "R240")
      (value "300R 1% 0402")
      (footprint "RESC0402(1005)_L")
      (description "300R 0.063W 1% 0402 (1005 Metric)  SMD")
      (fields (field (name "TOLERANCE") "1 %") (field (name "POWER") "0.063 W"))
      (libsource (lib "Altium Content Vault") (part "RES"))
    )
    (comp (ref "R241")
      (value "18R 1% 0402")
      (footprint "RESC0402(1005)_L")
      (description "18R 0.063W 1% 0402 (1005 Metric)  SMD")
      (fields (field (name "TOLERANCE") "1 %") (field (name "POWER") "0.063 W"))
      (libsource (lib "Altium Content Vault") (part "RES"))
    )
    (comp (ref "R242")
      (value "18R 1% 0402")
      (footprint "RESC0402(1005)_L")
      (description "18R 0.063W 1% 0402 (1005 Metric)  SMD")
      (fields (field (name "TOLERANCE") "1 %") (field (name "POWER") "0.063 W"))
      (libsource (lib "Altium Content Vault") (part "RES"))
    )
    (comp (ref "R243")
      (value "300R 1% 0402")
      (footprint "RESC0402(1005)_L")
      (description "300R 0.063W 1% 0402 (1005 Metric)  SMD")
      (fields (field (name "TOLERANCE") "1 %") (field (name "POWER") "0.063 W"))
      (libsource (lib "Altium Content Vault") (part "RES"))
    )
    (comp (ref "R244")
      (value "300R 1% 0402")
      (footprint "RESC0402(1005)_L")
      (description "300R 0.063W 1% 0402 (1005 Metric)  SMD")
      (fields (field (name "TOLERANCE") "1 %") (field (name "POWER") "0.063 W"))
      (libsource (lib "Altium Content Vault") (part "RES"))
    )
    (comp (ref "R245")
      (value "300R 1% 0402")
      (footprint "RESC0402(1005)_L")
      (description "300R 0.063W 1% 0402 (1005 Metric)  SMD")
      (fields (field (name "TOLERANCE") "1 %") (field (name "POWER") "0.063 W"))
      (libsource (lib "Altium Content Vault") (part "RES"))
    )
    (comp (ref "R246")
      (value "300R 1% 0402")
      (footprint "RESC0402(1005)_L")
      (description "300R 0.063W 1% 0402 (1005 Metric)  SMD")
      (fields (field (name "TOLERANCE") "1 %") (field (name "POWER") "0.063 W"))
      (libsource (lib "Altium Content Vault") (part "RES"))
    )
    (comp (ref "R247")
      (value "18R 1% 0402")
      (footprint "RESC0402(1005)_L")
      (description "18R 0.063W 1% 0402 (1005 Metric)  SMD")
      (fields (field (name "TOLERANCE") "1 %") (field (name "POWER") "0.063 W"))
      (libsource (lib "Altium Content Vault") (part "RES"))
    )
    (comp (ref "R248")
      (value "300R 1% 0402")
      (footprint "RESC0402(1005)_L")
      (description "300R 0.063W 1% 0402 (1005 Metric)  SMD")
      (fields (field (name "TOLERANCE") "1 %") (field (name "POWER") "0.063 W"))
      (libsource (lib "Altium Content Vault") (part "RES"))
    )
    (comp (ref "R249")
      (value "300R 1% 0402")
      (footprint "RESC0402(1005)_L")
      (description "300R 0.063W 1% 0402 (1005 Metric)  SMD")
      (fields (field (name "TOLERANCE") "1 %") (field (name "POWER") "0.063 W"))
      (libsource (lib "Altium Content Vault") (part "RES"))
    )
  )
  (nets
    (net (code "1") (name "/TCA_CLK0") (class "Default")
      (node (ref "C293") (pin "2") (pinfunction "2_2") (pintype "passive"))
      (node (ref "L10") (pin "1") (pinfunction "1_1") (pintype "passive"))
    )
    (net (code "2") (name "/TCA_CLK1") (class "Default")
      (node (ref "C301") (pin "2") (pinfunction "2_2") (pintype "passive"))
      (node (ref "L16") (pin "1") (pinfunction "1_1") (pintype "passive"))
    )
    (net (code "3") (name "/TCA_CLK2") (class "Default")
      (node (ref "C309") (pin "2") (pinfunction "2_2") (pintype "passive"))
      (node (ref "L22") (pin "1") (pinfunction "1_1") (pintype "passive"))
    )
    (net (code "4") (name "/TCA_CLK3") (class "Default")
      (node (ref "C317") (pin "2") (pinfunction "2_2") (pintype "passive"))
      (node (ref "L28") (pin "1") (pinfunction "1_1") (pintype "passive"))
    )
    (net (code "5") (name "/TCA_CLK4") (class "Default")
      (node (ref "C325") (pin "2") (pinfunction "2_2") (pintype "passive"))
      (node (ref "L34") (pin "1") (pinfunction "1_1") (pintype "passive"))
    )
    (net (code "6") (name "/TCA_CLK5") (class "Default")
      (node (ref "C297") (pin "2") (pinfunction "2_2") (pintype "passive"))
      (node (ref "L13") (pin "1") (pinfunction "1_1") (pintype "passive"))
    )
    (net (code "7") (name "/TCA_CLK6") (class "Default")
      (node (ref "C305") (pin "2") (pinfunction "2_2") (pintype "passive"))
      (node (ref "L19") (pin "1") (pinfunction "1_1") (pintype "passive"))
    )
    (net (code "8") (name "/TCA_CLK7") (class "Default")
      (node (ref "C313") (pin "2") (pinfunction "2_2") (pintype "passive"))
      (node (ref "L25") (pin "1") (pinfunction "1_1") (pintype "passive"))
    )
    (net (code "9") (name "/TCA_CLK8") (class "Default")
      (node (ref "C321") (pin "2") (pinfunction "2_2") (pintype "passive"))
      (node (ref "L31") (pin "1") (pinfunction "1_1") (pintype "passive"))
    )
    (net (code "10") (name "/TC_SINUS_0") (class "Default")
      (node (ref "R223") (pin "2") (pinfunction "2_2") (pintype "passive"))
      (node (ref "R226") (pin "2") (pinfunction "2_2") (pintype "passive"))
    )
    (net (code "11") (name "/TC_SINUS_1") (class "Default")
      (node (ref "R229") (pin "2") (pinfunction "2_2") (pintype "passive"))
      (node (ref "R232") (pin "2") (pinfunction "2_2") (pintype "passive"))
    )
    (net (code "12") (name "/TC_SINUS_2") (class "Default")
      (node (ref "R235") (pin "2") (pinfunction "2_2") (pintype "passive"))
      (node (ref "R238") (pin "2") (pinfunction "2_2") (pintype "passive"))
    )
    (net (code "13") (name "/TC_SINUS_3") (class "Default")
      (node (ref "R241") (pin "2") (pinfunction "2_2") (pintype "passive"))
      (node (ref "R244") (pin "2") (pinfunction "2_2") (pintype "passive"))
    )
    (net (code "14") (name "/TC_SINUS_4") (class "Default")
      (node (ref "R247") (pin "2") (pinfunction "2_2") (pintype "passive"))
      (node (ref "R249") (pin "2") (pinfunction "2_2") (pintype "passive"))
    )
    (net (code "15") (name "/TC_SINUS_5") (class "Default")
      (node (ref "R224") (pin "2") (pinfunction "2_2") (pintype "passive"))
      (node (ref "R228") (pin "2") (pinfunction "2_2") (pintype "passive"))
    )
    (net (code "16") (name "/TC_SINUS_6") (class "Default")
      (node (ref "R230") (pin "2") (pinfunction "2_2") (pintype "passive"))
      (node (ref "R233") (pin "2") (pinfunction "2_2") (pintype "passive"))
    )
    (net (code "17") (name "/TC_SINUS_7") (class "Default")
      (node (ref "R236") (pin "2") (pinfunction "2_2") (pintype "passive"))
      (node (ref "R239") (pin "2") (pinfunction "2_2") (pintype "passive"))
    )
    (net (code "18") (name "/TC_SINUS_8") (class "Default")
      (node (ref "R242") (pin "2") (pinfunction "2_2") (pintype "passive"))
      (node (ref "R246") (pin "2") (pinfunction "2_2") (pintype "passive"))
    )
    (net (code "19") (name "Net-(C294-Pad2)") (class "Default")
      (node (ref "C294") (pin "2") (pinfunction "2_2") (pintype "passive"))
      (node (ref "L10") (pin "2") (pinfunction "2_2") (pintype "passive"))
      (node (ref "L11") (pin "1") (pinfunction "1_1") (pintype "passive"))
    )
    (net (code "20") (name "Net-(C295-Pad2)") (class "Default")
      (node (ref "C295") (pin "2") (pinfunction "2_2") (pintype "passive"))
      (node (ref "L11") (pin "2") (pinfunction "2_2") (pintype "passive"))
      (node (ref "L12") (pin "1") (pinfunction "1_1") (pintype "passive"))
    )
    (net (code "21") (name "Net-(C296-Pad2)") (class "Default")
      (node (ref "C296") (pin "2") (pinfunction "2_2") (pintype "passive"))
      (node (ref "L12") (pin "2") (pinfunction "2_2") (pintype "passive"))
      (node (ref "R223") (pin "1") (pinfunction "1_1") (pintype "passive"))
      (node (ref "R225") (pin "2") (pinfunction "2_2") (pintype "passive"))
    )
    (net (code "22") (name "Net-(C298-Pad2)") (class "Default")
      (node (ref "C298") (pin "2") (pinfunction "2_2") (pintype "passive"))
      (node (ref "L13") (pin "2") (pinfunction "2_2") (pintype "passive"))
      (node (ref "L14") (pin "1") (pinfunction "1_1") (pintype "passive"))
    )
    (net (code "23") (name "Net-(C299-Pad2)") (class "Default")
      (node (ref "C299") (pin "2") (pinfunction "2_2") (pintype "passive"))
      (node (ref "L14") (pin "2") (pinfunction "2_2") (pintype "passive"))
      (node (ref "L15") (pin "1") (pinfunction "1_1") (pintype "passive"))
    )
    (net (code "24") (name "Net-(C300-Pad2)") (class "Default")
      (node (ref "C300") (pin "2") (pinfunction "2_2") (pintype "passive"))
      (node (ref "L15") (pin "2") (pinfunction "2_2") (pintype "passive"))
      (node (ref "R224") (pin "1") (pinfunction "1_1") (pintype "passive"))
      (node (ref "R227") (pin "2") (pinfunction "2_2") (pintype "passive"))
    )
    (net (code "25") (name "Net-(C302-Pad2)") (class "Default")
      (node (ref "C302") (pin "2") (pinfunction "2_2") (pintype "passive"))
      (node (ref "L16") (pin "2") (pinfunction "2_2") (pintype "passive"))
      (node (ref "L17") (pin "1") (pinfunction "1_1") (pintype "passive"))
    )
    (net (code "26") (name "Net-(C303-Pad2)") (class "Default")
      (node (ref "C303") (pin "2") (pinfunction "2_2") (pintype "passive"))
      (node (ref "L17") (pin "2") (pinfunction "2_2") (pintype "passive"))
      (node (ref "L18") (pin "1") (pinfunction "1_1") (pintype "passive"))
    )
    (net (code "27") (name "Net-(C304-Pad2)") (class "Default")
      (node (ref "C304") (pin "2") (pinfunction "2_2") (pintype "passive"))
      (node (ref "L18") (pin "2") (pinfunction "2_2") (pintype "passive"))
      (node (ref "R229") (pin "1") (pinfunction "1_1") (pintype "passive"))
      (node (ref "R231") (pin "2") (pinfunction "2_2") (pintype "passive"))
    )
    (net (code "28") (name "Net-(C306-Pad2)") (class "Default")
      (node (ref "C306") (pin "2") (pinfunction "2_2") (pintype "passive"))
      (node (ref "L19") (pin "2") (pinfunction "2_2") (pintype "passive"))
      (node (ref "L20") (pin "1") (pinfunction "1_1") (pintype "passive"))
    )
    (net (code "29") (name "Net-(C307-Pad2)") (class "Default")
      (node (ref "C307") (pin "2") (pinfunction "2_2") (pintype "passive"))
      (node (ref "L20") (pin "2") (pinfunction "2_2") (pintype "passive"))
      (node (ref "L21") (pin "1") (pinfunction "1_1") (pintype "passive"))
    )
    (net (code "30") (name "Net-(C308-Pad2)") (class "Default")
      (node (ref "C308") (pin "2") (pinfunction "2_2") (pintype "passive"))
      (node (ref "L21") (pin "2") (pinfunction "2_2") (pintype "passive"))
      (node (ref "R230") (pin "1") (pinfunction "1_1") (pintype "passive"))
      (node (ref "R234") (pin "2") (pinfunction "2_2") (pintype "passive"))
    )
    (net (code "31") (name "Net-(C310-Pad2)") (class "Default")
      (node (ref "C310") (pin "2") (pinfunction "2_2") (pintype "passive"))
      (node (ref "L22") (pin "2") (pinfunction "2_2") (pintype "passive"))
      (node (ref "L23") (pin "1") (pinfunction "1_1") (pintype "passive"))
    )
    (net (code "32") (name "Net-(C311-Pad2)") (class "Default")
      (node (ref "C311") (pin "2") (pinfunction "2_2") (pintype "passive"))
      (node (ref "L23") (pin "2") (pinfunction "2_2") (pintype "passive"))
      (node (ref "L24") (pin "1") (pinfunction "1_1") (pintype "passive"))
    )
    (net (code "33") (name "Net-(C312-Pad2)") (class "Default")
      (node (ref "C312") (pin "2") (pinfunction "2_2") (pintype "passive"))
      (node (ref "L24") (pin "2") (pinfunction "2_2") (pintype "passive"))
      (node (ref "R235") (pin "1") (pinfunction "1_1") (pintype "passive"))
      (node (ref "R237") (pin "2") (pinfunction "2_2") (pintype "passive"))
    )
    (net (code "34") (name "Net-(C314-Pad2)") (class "Default")
      (node (ref "C314") (pin "2") (pinfunction "2_2") (pintype "passive"))
      (node (ref "L25") (pin "2") (pinfunction "2_2") (pintype "passive"))
      (node (ref "L26") (pin "1") (pinfunction "1_1") (pintype "passive"))
    )
    (net (code "35") (name "Net-(C315-Pad2)") (class "Default")
      (node (ref "C315") (pin "2") (pinfunction "2_2") (pintype "passive"))
      (node (ref "L26") (pin "2") (pinfunction "2_2") (pintype "passive"))
      (node (ref "L27") (pin "1") (pinfunction "1_1") (pintype "passive"))
    )
    (net (code "36") (name "Net-(C316-Pad2)") (class "Default")
      (node (ref "C316") (pin "2") (pinfunction "2_2") (pintype "passive"))
      (node (ref "L27") (pin "2") (pinfunction "2_2") (pintype "passive"))
      (node (ref "R236") (pin "1") (pinfunction "1_1") (pintype "passive"))
      (node (ref "R240") (pin "2") (pinfunction "2_2") (pintype "passive"))
    )
    (net (code "37") (name "Net-(C318-Pad2)") (class "Default")
      (node (ref "C318") (pin "2") (pinfunction "2_2") (pintype "passive"))
      (node (ref "L28") (pin "2") (pinfunction "2_2") (pintype "passive"))
      (node (ref "L29") (pin "1") (pinfunction "1_1") (pintype "passive"))
    )
    (net (code "38") (name "Net-(C319-Pad2)") (class "Default")
      (node (ref "C319") (pin "2") (pinfunction "2_2") (pintype "passive"))
      (node (ref "L29") (pin "2") (pinfunction "2_2") (pintype "passive"))
      (node (ref "L30") (pin "1") (pinfunction "1_1") (pintype "passive"))
    )
    (net (code "39") (name "Net-(C320-Pad2)") (class "Default")
      (node (ref "C320") (pin "2") (pinfunction "2_2") (pintype "passive"))
      (node (ref "L30") (pin "2") (pinfunction "2_2") (pintype "passive"))
      (node (ref "R241") (pin "1") (pinfunction "1_1") (pintype "passive"))
      (node (ref "R243") (pin "2") (pinfunction "2_2") (pintype "passive"))
    )
    (net (code "40") (name "Net-(C322-Pad2)") (class "Default")
      (node (ref "C322") (pin "2") (pinfunction "2_2") (pintype "passive"))
      (node (ref "L31") (pin "2") (pinfunction "2_2") (pintype "passive"))
      (node (ref "L32") (pin "1") (pinfunction "1_1") (pintype "passive"))
    )
    (net (code "41") (name "Net-(C323-Pad2)") (class "Default")
      (node (ref "C323") (pin "2") (pinfunction "2_2") (pintype "passive"))
      (node (ref "L32") (pin "2") (pinfunction "2_2") (pintype "passive"))
      (node (ref "L33") (pin "1") (pinfunction "1_1") (pintype "passive"))
    )
    (net (code "42") (name "Net-(C324-Pad2)") (class "Default")
      (node (ref "C324") (pin "2") (pinfunction "2_2") (pintype "passive"))
      (node (ref "L33") (pin "2") (pinfunction "2_2") (pintype "passive"))
      (node (ref "R242") (pin "1") (pinfunction "1_1") (pintype "passive"))
      (node (ref "R245") (pin "2") (pinfunction "2_2") (pintype "passive"))
    )
    (net (code "43") (name "Net-(C326-Pad2)") (class "Default")
      (node (ref "C326") (pin "2") (pinfunction "2_2") (pintype "passive"))
      (node (ref "L34") (pin "2") (pinfunction "2_2") (pintype "passive"))
      (node (ref "L35") (pin "1") (pinfunction "1_1") (pintype "passive"))
    )
    (net (code "44") (name "Net-(C327-Pad2)") (class "Default")
      (node (ref "C327") (pin "2") (pinfunction "2_2") (pintype "passive"))
      (node (ref "L35") (pin "2") (pinfunction "2_2") (pintype "passive"))
      (node (ref "L36") (pin "1") (pinfunction "1_1") (pintype "passive"))
    )
    (net (code "45") (name "Net-(C328-Pad2)") (class "Default")
      (node (ref "C328") (pin "2") (pinfunction "2_2") (pintype "passive"))
      (node (ref "L36") (pin "2") (pinfunction "2_2") (pintype "passive"))
      (node (ref "R247") (pin "1") (pinfunction "1_1") (pintype "passive"))
      (node (ref "R248") (pin "2") (pinfunction "2_2") (pintype "passive"))
    )
    (net (code "46") (name "TRB_GND") (class "Default")
      (node (ref "C293") (pin "1") (pinfunction "1_1") (pintype "passive"))
      (node (ref "C294") (pin "1") (pinfunction "1_1") (pintype "passive"))
      (node (ref "C295") (pin "1") (pinfunction "1_1") (pintype "passive"))
      (node (ref "C296") (pin "1") (pinfunction "1_1") (pintype "passive"))
      (node (ref "C297") (pin "1") (pinfunction "1_1") (pintype "passive"))
      (node (ref "C298") (pin "1") (pinfunction "1_1") (pintype "passive"))
      (node (ref "C299") (pin "1") (pinfunction "1_1") (pintype "passive"))
      (node (ref "C300") (pin "1") (pinfunction "1_1") (pintype "passive"))
      (node (ref "C301") (pin "1") (pinfunction "1_1") (pintype "passive"))
      (node (ref "C302") (pin "1") (pinfunction "1_1") (pintype "passive"))
      (node (ref "C303") (pin "1") (pinfunction "1_1") (pintype "passive"))
      (node (ref "C304") (pin "1") (pinfunction "1_1") (pintype "passive"))
      (node (ref "C305") (pin "1") (pinfunction "1_1") (pintype "passive"))
      (node (ref "C306") (pin "1") (pinfunction "1_1") (pintype "passive"))
      (node (ref "C307") (pin "1") (pinfunction "1_1") (pintype "passive"))
      (node (ref "C308") (pin "1") (pinfunction "1_1") (pintype "passive"))
      (node (ref "C309") (pin "1") (pinfunction "1_1") (pintype "passive"))
      (node (ref "C310") (pin "1") (pinfunction "1_1") (pintype "passive"))
      (node (ref "C311") (pin "1") (pinfunction "1_1") (pintype "passive"))
      (node (ref "C312") (pin "1") (pinfunction "1_1") (pintype "passive"))
      (node (ref "C313") (pin "1") (pinfunction "1_1") (pintype "passive"))
      (node (ref "C314") (pin "1") (pinfunction "1_1") (pintype "passive"))
      (node (ref "C315") (pin "1") (pinfunction "1_1") (pintype "passive"))
      (node (ref "C316") (pin "1") (pinfunction "1_1") (pintype "passive"))
      (node (ref "C317") (pin "1") (pinfunction "1_1") (pintype "passive"))
      (node (ref "C318") (pin "1") (pinfunction "1_1") (pintype "passive"))
      (node (ref "C319") (pin "1") (pinfunction "1_1") (pintype "passive"))
      (node (ref "C320") (pin "1") (pinfunction "1_1") (pintype "passive"))
      (node (ref "C321") (pin "1") (pinfunction "1_1") (pintype "passive"))
      (node (ref "C322") (pin "1") (pinfunction "1_1") (pintype "passive"))
      (node (ref "C323") (pin "1") (pinfunction "1_1") (pintype "passive"))
      (node (ref "C324") (pin "1") (pinfunction "1_1") (pintype "passive"))
      (node (ref "C325") (pin "1") (pinfunction "1_1") (pintype "passive"))
      (node (ref "C326") (pin "1") (pinfunction "1_1") (pintype "passive"))
      (node (ref "C327") (pin "1") (pinfunction "1_1") (pintype "passive"))
      (node (ref "C328") (pin "1") (pinfunction "1_1") (pintype "passive"))
      (node (ref "R225") (pin "1") (pinfunction "1_1") (pintype "passive"))
      (node (ref "R226") (pin "1") (pinfunction "1_1") (pintype "passive"))
      (node (ref "R227") (pin "1") (pinfunction "1_1") (pintype "passive"))
      (node (ref "R228") (pin "1") (pinfunction "1_1") (pintype "passive"))
      (node (ref "R231") (pin "1") (pinfunction "1_1") (pintype "passive"))
      (node (ref "R232") (pin "1") (pinfunction "1_1") (pintype "passive"))
      (node (ref "R233") (pin "1") (pinfunction "1_1") (pintype "passive"))
      (node (ref "R234") (pin "1") (pinfunction "1_1") (pintype "passive"))
      (node (ref "R237") (pin "1") (pinfunction "1_1") (pintype "passive"))
      (node (ref "R238") (pin "1") (pinfunction "1_1") (pintype "passive"))
      (node (ref "R239") (pin "1") (pinfunction "1_1") (pintype "passive"))
      (node (ref "R240") (pin "1") (pinfunction "1_1") (pintype "passive"))
      (node (ref "R243") (pin "1") (pinfunction "1_1") (pintype "passive"))
      (node (ref "R244") (pin "1") (pinfunction "1_1") (pintype "passive"))
      (node (ref "R245") (pin "1") (pinfunction "1_1") (pintype "passive"))
      (node (ref "R246") (pin "1") (pinfunction "1_1") (pintype "passive"))
      (node (ref "R248") (pin "1") (pinfunction "1_1") (pintype "passive"))
      (node (ref "R249") (pin "1") (pinfunction "1_1") (pintype "passive"))
    )
  )
)
